# omnibus_proto.net
KiCad netlist of a schematic drawn in EAGLE
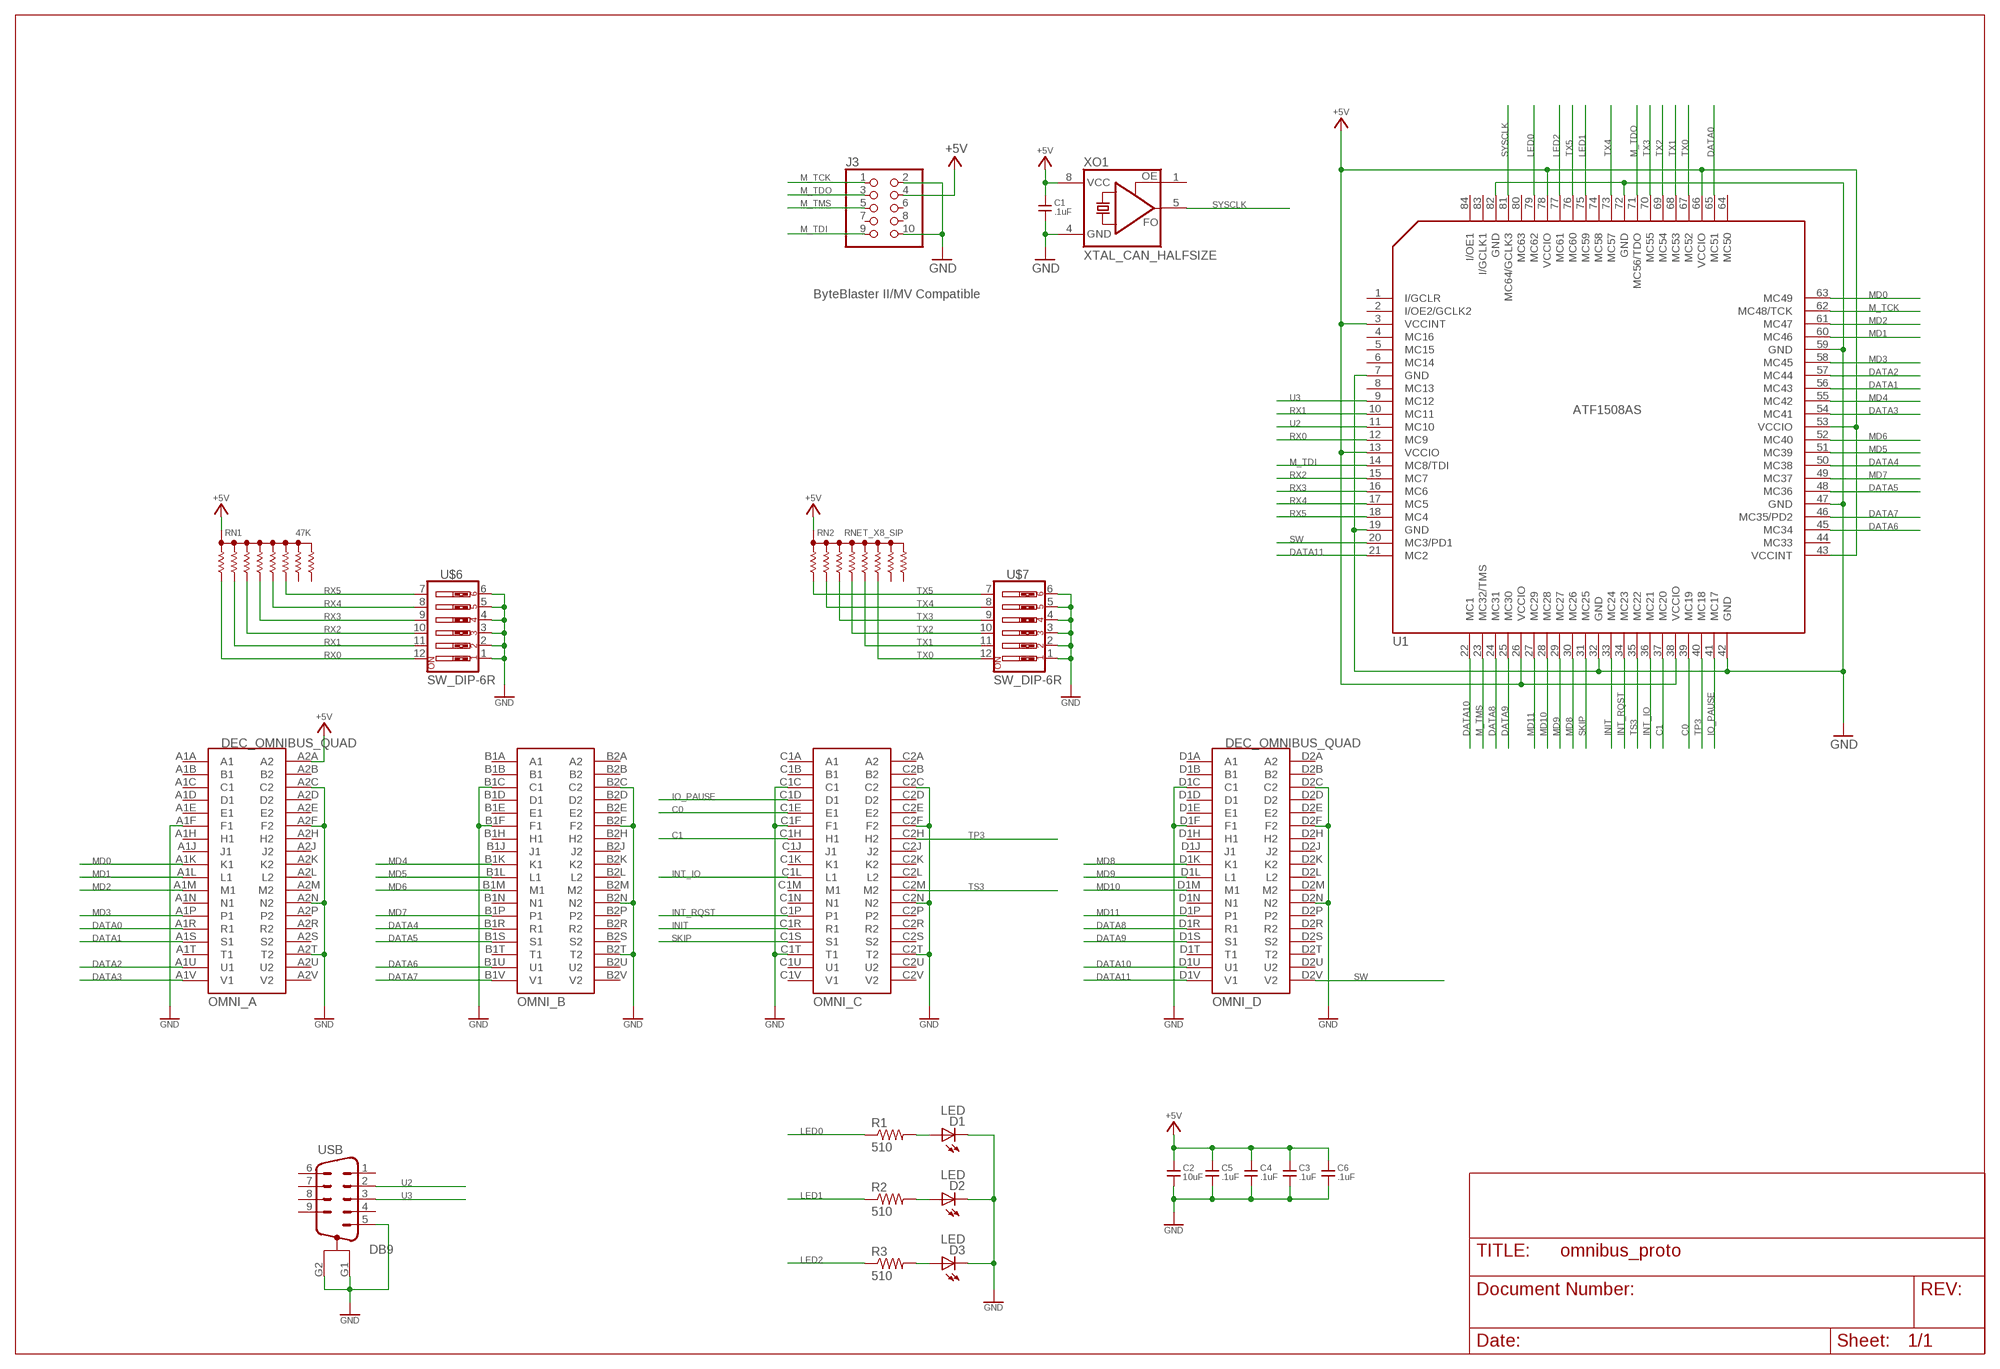
[diagram p0: schematic, sheet 1]

(export (version "E")
  (design (tool "Eeschema 10.0.6"))
  (components
    (comp (ref "C1")
      (value ".1uF")
      (footprint "eagle-import:C_TH_5MM")
      (libsource (lib "eagle-import") (part "C_US"))
    )
    (comp (ref "C2")
      (value "10uF")
      (footprint "eagle-import:C_TH_5MM")
      (libsource (lib "eagle-import") (part "C_US"))
    )
    (comp (ref "C3")
      (value ".1uF")
      (footprint "eagle-import:C_TH_5MM")
      (libsource (lib "eagle-import") (part "C_US"))
    )
    (comp (ref "C4")
      (value ".1uF")
      (footprint "eagle-import:C_TH_5MM")
      (libsource (lib "eagle-import") (part "C_US"))
    )
    (comp (ref "C5")
      (value ".1uF")
      (footprint "eagle-import:C_TH_5MM")
      (libsource (lib "eagle-import") (part "C_US"))
    )
    (comp (ref "C6")
      (value ".1uF")
      (footprint "eagle-import:C_TH_5MM")
      (libsource (lib "eagle-import") (part "C_US"))
    )
    (comp (ref "D1")
      (value "LED")
      (footprint "eagle-import:LED_TH_3MM")
      (libsource (lib "eagle-import") (part "LED"))
    )
    (comp (ref "D2")
      (value "LED")
      (footprint "eagle-import:LED_TH_3MM")
      (libsource (lib "eagle-import") (part "LED"))
    )
    (comp (ref "D3")
      (value "LED")
      (footprint "eagle-import:LED_TH_3MM")
      (libsource (lib "eagle-import") (part "LED"))
    )
    (comp (ref "J3")
      (value "HDR_2X5\"")
      (footprint "eagle-import:HDR_2X5")
      (libsource (lib "eagle-import") (part "HDR_2X5{dblquote}"))
    )
    (comp (ref "OMNI")
      (value "DEC_OMNIBUS_QUAD")
      (footprint "eagle-import:DEC_OMNIBUS_QUAD")
      (libsource (lib "eagle-import") (part "DEC_OMNIBUS_QUAD"))
    )
    (comp (ref "R1")
      (value "510")
      (footprint "eagle-import:R_204_7")
      (libsource (lib "eagle-import") (part "R_US"))
    )
    (comp (ref "R2")
      (value "510")
      (footprint "eagle-import:R_204_7")
      (libsource (lib "eagle-import") (part "R_US"))
    )
    (comp (ref "R3")
      (value "510")
      (footprint "eagle-import:R_204_7")
      (libsource (lib "eagle-import") (part "R_US"))
    )
    (comp (ref "RN1")
      (value "47K")
      (footprint "eagle-import:RN_SIP9")
      (libsource (lib "eagle-import") (part "RNET_X8_SIP"))
    )
    (comp (ref "RN2")
      (value "RNET_X8_SIP")
      (footprint "eagle-import:RN_SIP9")
      (libsource (lib "eagle-import") (part "RNET_X8_SIP"))
    )
    (comp (ref "U$6")
      (value "SW_DIP-6R")
      (footprint "eagle-import:SW_DIP-6_ROUND")
      (libsource (lib "eagle-import") (part "SW_DIP-6R"))
    )
    (comp (ref "U$7")
      (value "SW_DIP-6R")
      (footprint "eagle-import:SW_DIP-6_ROUND")
      (libsource (lib "eagle-import") (part "SW_DIP-6R"))
    )
    (comp (ref "U1")
      (value "ATF1508AS")
      (footprint "eagle-import:PLCC84")
      (libsource (lib "eagle-import") (part "ATF1504AS_PLCC"))
    )
    (comp (ref "USB")
      (value "DB9")
      (footprint "eagle-import:AMP_DB-9RA")
      (fields (field (name "MANF") "TE/AMP"))
      (libsource (lib "eagle-import") (part "DB9"))
    )
    (comp (ref "XO1")
      (value "XTAL_CAN_HALFSIZE")
      (footprint "eagle-import:XTAL_CAN_HALFSIZE")
      (libsource (lib "eagle-import") (part "XTAL_CAN_HALFSIZE"))
    )
  )
  (nets
    (net (code "1") (name "+5V") (class "Default")
      (node (ref "C1") (pin "1") (pinfunction "1_1") (pintype "passive"))
      (node (ref "C2") (pin "1") (pinfunction "1_1") (pintype "passive"))
      (node (ref "C3") (pin "1") (pinfunction "1_1") (pintype "passive"))
      (node (ref "C4") (pin "1") (pinfunction "1_1") (pintype "passive"))
      (node (ref "C5") (pin "1") (pinfunction "1_1") (pintype "passive"))
      (node (ref "C6") (pin "1") (pinfunction "1_1") (pintype "passive"))
      (node (ref "J3") (pin "4") (pinfunction "4_4") (pintype "passive"))
      (node (ref "OMNI") (pin "A2A") (pinfunction "A2_A2A") (pintype "passive"))
      (node (ref "RN1") (pin "1") (pinfunction "1_1") (pintype "passive"))
      (node (ref "RN2") (pin "1") (pinfunction "1_1") (pintype "passive"))
      (node (ref "U1") (pin "13") (pinfunction "VCCIO_13") (pintype "bidirectional"))
      (node (ref "U1") (pin "26") (pinfunction "VCCIO_26") (pintype "bidirectional"))
      (node (ref "U1") (pin "3") (pinfunction "VCCINT_3") (pintype "bidirectional"))
      (node (ref "U1") (pin "38") (pinfunction "VCCIO_38") (pintype "bidirectional"))
      (node (ref "U1") (pin "43") (pinfunction "VCCINT_43") (pintype "bidirectional"))
      (node (ref "U1") (pin "53") (pinfunction "VCCIO_53") (pintype "bidirectional"))
      (node (ref "U1") (pin "66") (pinfunction "VCCIO_66") (pintype "bidirectional"))
      (node (ref "U1") (pin "78") (pinfunction "VCCIO_78") (pintype "bidirectional"))
      (node (ref "XO1") (pin "8") (pinfunction "VCC_8") (pintype "power_in"))
    )
    (net (code "2") (name "/C0") (class "Default")
      (node (ref "OMNI") (pin "C1E") (pinfunction "E1_C1E") (pintype "passive"))
      (node (ref "U1") (pin "39") (pinfunction "MC19_39") (pintype "bidirectional"))
    )
    (net (code "3") (name "/C1") (class "Default")
      (node (ref "OMNI") (pin "C1H") (pinfunction "H1_C1H") (pintype "passive"))
      (node (ref "U1") (pin "37") (pinfunction "MC20_37") (pintype "bidirectional"))
    )
    (net (code "4") (name "/DATA0") (class "Default")
      (node (ref "OMNI") (pin "A1R") (pinfunction "R1_A1R") (pintype "passive"))
      (node (ref "U1") (pin "65") (pinfunction "MC51_65") (pintype "bidirectional"))
    )
    (net (code "5") (name "/DATA1") (class "Default")
      (node (ref "OMNI") (pin "A1S") (pinfunction "S1_A1S") (pintype "passive"))
      (node (ref "U1") (pin "56") (pinfunction "MC43_56") (pintype "bidirectional"))
    )
    (net (code "6") (name "/DATA2") (class "Default")
      (node (ref "OMNI") (pin "A1U") (pinfunction "U1_A1U") (pintype "passive"))
      (node (ref "U1") (pin "57") (pinfunction "MC44_57") (pintype "bidirectional"))
    )
    (net (code "7") (name "/DATA3") (class "Default")
      (node (ref "OMNI") (pin "A1V") (pinfunction "V1_A1V") (pintype "passive"))
      (node (ref "U1") (pin "54") (pinfunction "MC41_54") (pintype "bidirectional"))
    )
    (net (code "8") (name "/DATA4") (class "Default")
      (node (ref "OMNI") (pin "B1R") (pinfunction "R1_B1R") (pintype "passive"))
      (node (ref "U1") (pin "50") (pinfunction "MC38_50") (pintype "bidirectional"))
    )
    (net (code "9") (name "/DATA5") (class "Default")
      (node (ref "OMNI") (pin "B1S") (pinfunction "S1_B1S") (pintype "passive"))
      (node (ref "U1") (pin "48") (pinfunction "MC36_48") (pintype "bidirectional"))
    )
    (net (code "10") (name "/DATA6") (class "Default")
      (node (ref "OMNI") (pin "B1U") (pinfunction "U1_B1U") (pintype "passive"))
      (node (ref "U1") (pin "45") (pinfunction "MC34_45") (pintype "bidirectional"))
    )
    (net (code "11") (name "/DATA7") (class "Default")
      (node (ref "OMNI") (pin "B1V") (pinfunction "V1_B1V") (pintype "passive"))
      (node (ref "U1") (pin "46") (pinfunction "MC35/PD2_46") (pintype "bidirectional"))
    )
    (net (code "12") (name "/DATA8") (class "Default")
      (node (ref "OMNI") (pin "D1R") (pinfunction "R1_D1R") (pintype "passive"))
      (node (ref "U1") (pin "24") (pinfunction "MC31_24") (pintype "bidirectional"))
    )
    (net (code "13") (name "/DATA9") (class "Default")
      (node (ref "OMNI") (pin "D1S") (pinfunction "S1_D1S") (pintype "passive"))
      (node (ref "U1") (pin "25") (pinfunction "MC30_25") (pintype "bidirectional"))
    )
    (net (code "14") (name "/DATA10") (class "Default")
      (node (ref "OMNI") (pin "D1U") (pinfunction "U1_D1U") (pintype "passive"))
      (node (ref "U1") (pin "22") (pinfunction "MC1_22") (pintype "bidirectional"))
    )
    (net (code "15") (name "/DATA11") (class "Default")
      (node (ref "OMNI") (pin "D1V") (pinfunction "V1_D1V") (pintype "passive"))
      (node (ref "U1") (pin "21") (pinfunction "MC2_21") (pintype "bidirectional"))
    )
    (net (code "16") (name "/INIT") (class "Default")
      (node (ref "OMNI") (pin "C1R") (pinfunction "R1_C1R") (pintype "passive"))
      (node (ref "U1") (pin "33") (pinfunction "MC24_33") (pintype "bidirectional"))
    )
    (net (code "17") (name "/INT_IO") (class "Default")
      (node (ref "OMNI") (pin "C1L") (pinfunction "L1_C1L") (pintype "passive"))
      (node (ref "U1") (pin "36") (pinfunction "MC21_36") (pintype "bidirectional"))
    )
    (net (code "18") (name "/INT_RQST") (class "Default")
      (node (ref "OMNI") (pin "C1P") (pinfunction "P1_C1P") (pintype "passive"))
      (node (ref "U1") (pin "34") (pinfunction "MC23_34") (pintype "bidirectional"))
    )
    (net (code "19") (name "/IO_PAUSE") (class "Default")
      (node (ref "OMNI") (pin "C1D") (pinfunction "D1_C1D") (pintype "passive"))
      (node (ref "U1") (pin "41") (pinfunction "MC17_41") (pintype "bidirectional"))
    )
    (net (code "20") (name "/LED0") (class "Default")
      (node (ref "R1") (pin "1") (pinfunction "1_1") (pintype "passive"))
      (node (ref "U1") (pin "79") (pinfunction "MC62_79") (pintype "bidirectional"))
    )
    (net (code "21") (name "/LED1") (class "Default")
      (node (ref "R2") (pin "1") (pinfunction "1_1") (pintype "passive"))
      (node (ref "U1") (pin "75") (pinfunction "MC59_75") (pintype "bidirectional"))
    )
    (net (code "22") (name "/LED2") (class "Default")
      (node (ref "R3") (pin "1") (pinfunction "1_1") (pintype "passive"))
      (node (ref "U1") (pin "77") (pinfunction "MC61_77") (pintype "bidirectional"))
    )
    (net (code "23") (name "/MD0") (class "Default")
      (node (ref "OMNI") (pin "A1K") (pinfunction "K1_A1K") (pintype "passive"))
      (node (ref "U1") (pin "63") (pinfunction "MC49_63") (pintype "bidirectional"))
    )
    (net (code "24") (name "/MD1") (class "Default")
      (node (ref "OMNI") (pin "A1L") (pinfunction "L1_A1L") (pintype "passive"))
      (node (ref "U1") (pin "60") (pinfunction "MC46_60") (pintype "bidirectional"))
    )
    (net (code "25") (name "/MD2") (class "Default")
      (node (ref "OMNI") (pin "A1M") (pinfunction "M1_A1M") (pintype "passive"))
      (node (ref "U1") (pin "61") (pinfunction "MC47_61") (pintype "bidirectional"))
    )
    (net (code "26") (name "/MD3") (class "Default")
      (node (ref "OMNI") (pin "A1P") (pinfunction "P1_A1P") (pintype "passive"))
      (node (ref "U1") (pin "58") (pinfunction "MC45_58") (pintype "bidirectional"))
    )
    (net (code "27") (name "/MD4") (class "Default")
      (node (ref "OMNI") (pin "B1K") (pinfunction "K1_B1K") (pintype "passive"))
      (node (ref "U1") (pin "55") (pinfunction "MC42_55") (pintype "bidirectional"))
    )
    (net (code "28") (name "/MD5") (class "Default")
      (node (ref "OMNI") (pin "B1L") (pinfunction "L1_B1L") (pintype "passive"))
      (node (ref "U1") (pin "51") (pinfunction "MC39_51") (pintype "bidirectional"))
    )
    (net (code "29") (name "/MD6") (class "Default")
      (node (ref "OMNI") (pin "B1M") (pinfunction "M1_B1M") (pintype "passive"))
      (node (ref "U1") (pin "52") (pinfunction "MC40_52") (pintype "bidirectional"))
    )
    (net (code "30") (name "/MD7") (class "Default")
      (node (ref "OMNI") (pin "B1P") (pinfunction "P1_B1P") (pintype "passive"))
      (node (ref "U1") (pin "49") (pinfunction "MC37_49") (pintype "bidirectional"))
    )
    (net (code "31") (name "/MD8") (class "Default")
      (node (ref "OMNI") (pin "D1K") (pinfunction "K1_D1K") (pintype "passive"))
      (node (ref "U1") (pin "30") (pinfunction "MC26_30") (pintype "bidirectional"))
    )
    (net (code "32") (name "/MD9") (class "Default")
      (node (ref "OMNI") (pin "D1L") (pinfunction "L1_D1L") (pintype "passive"))
      (node (ref "U1") (pin "29") (pinfunction "MC27_29") (pintype "bidirectional"))
    )
    (net (code "33") (name "/MD10") (class "Default")
      (node (ref "OMNI") (pin "D1M") (pinfunction "M1_D1M") (pintype "passive"))
      (node (ref "U1") (pin "28") (pinfunction "MC28_28") (pintype "bidirectional"))
    )
    (net (code "34") (name "/MD11") (class "Default")
      (node (ref "OMNI") (pin "D1P") (pinfunction "P1_D1P") (pintype "passive"))
      (node (ref "U1") (pin "27") (pinfunction "MC29_27") (pintype "bidirectional"))
    )
    (net (code "35") (name "/M_TCK") (class "Default")
      (node (ref "J3") (pin "1") (pinfunction "1_1") (pintype "passive"))
      (node (ref "U1") (pin "62") (pinfunction "MC48/TCK_62") (pintype "bidirectional"))
    )
    (net (code "36") (name "/M_TDI") (class "Default")
      (node (ref "J3") (pin "9") (pinfunction "9_9") (pintype "passive"))
      (node (ref "U1") (pin "14") (pinfunction "MC8/TDI_14") (pintype "bidirectional"))
    )
    (net (code "37") (name "/M_TDO") (class "Default")
      (node (ref "J3") (pin "3") (pinfunction "3_3") (pintype "passive"))
      (node (ref "U1") (pin "71") (pinfunction "MC56/TDO_71") (pintype "bidirectional"))
    )
    (net (code "38") (name "/M_TMS") (class "Default")
      (node (ref "J3") (pin "5") (pinfunction "5_5") (pintype "passive"))
      (node (ref "U1") (pin "23") (pinfunction "MC32/TMS_23") (pintype "bidirectional"))
    )
    (net (code "39") (name "/RX0") (class "Default")
      (node (ref "RN1") (pin "2") (pinfunction "2_2") (pintype "passive"))
      (node (ref "U$6") (pin "12") (pinfunction "12_12") (pintype "passive"))
      (node (ref "U1") (pin "12") (pinfunction "MC9_12") (pintype "bidirectional"))
    )
    (net (code "40") (name "/RX1") (class "Default")
      (node (ref "RN1") (pin "3") (pinfunction "3_3") (pintype "passive"))
      (node (ref "U$6") (pin "11") (pinfunction "11_11") (pintype "passive"))
      (node (ref "U1") (pin "10") (pinfunction "MC11_10") (pintype "bidirectional"))
    )
    (net (code "41") (name "/RX2") (class "Default")
      (node (ref "RN1") (pin "4") (pinfunction "4_4") (pintype "passive"))
      (node (ref "U$6") (pin "10") (pinfunction "10_10") (pintype "passive"))
      (node (ref "U1") (pin "15") (pinfunction "MC7_15") (pintype "bidirectional"))
    )
    (net (code "42") (name "/RX3") (class "Default")
      (node (ref "RN1") (pin "5") (pinfunction "5_5") (pintype "passive"))
      (node (ref "U$6") (pin "9") (pinfunction "9_9") (pintype "passive"))
      (node (ref "U1") (pin "16") (pinfunction "MC6_16") (pintype "bidirectional"))
    )
    (net (code "43") (name "/RX4") (class "Default")
      (node (ref "RN1") (pin "6") (pinfunction "6_6") (pintype "passive"))
      (node (ref "U$6") (pin "8") (pinfunction "8_8") (pintype "passive"))
      (node (ref "U1") (pin "17") (pinfunction "MC5_17") (pintype "bidirectional"))
    )
    (net (code "44") (name "/RX5") (class "Default")
      (node (ref "RN1") (pin "7") (pinfunction "7_7") (pintype "passive"))
      (node (ref "U$6") (pin "7") (pinfunction "7_7") (pintype "passive"))
      (node (ref "U1") (pin "18") (pinfunction "MC4_18") (pintype "bidirectional"))
    )
    (net (code "45") (name "/SKIP") (class "Default")
      (node (ref "OMNI") (pin "C1S") (pinfunction "S1_C1S") (pintype "passive"))
      (node (ref "U1") (pin "31") (pinfunction "MC25_31") (pintype "bidirectional"))
    )
    (net (code "46") (name "/SW") (class "Default")
      (node (ref "OMNI") (pin "D2V") (pinfunction "V2_D2V") (pintype "passive"))
      (node (ref "U1") (pin "20") (pinfunction "MC3/PD1_20") (pintype "bidirectional"))
    )
    (net (code "47") (name "/SYSCLK") (class "Default")
      (node (ref "U1") (pin "81") (pinfunction "MC64/GCLK3_81") (pintype "bidirectional"))
      (node (ref "XO1") (pin "5") (pinfunction "FO_5") (pintype "output"))
    )
    (net (code "48") (name "/TP3") (class "Default")
      (node (ref "OMNI") (pin "C2H") (pinfunction "H2_C2H") (pintype "passive"))
      (node (ref "U1") (pin "40") (pinfunction "MC18_40") (pintype "bidirectional"))
    )
    (net (code "49") (name "/TS3") (class "Default")
      (node (ref "OMNI") (pin "C2M") (pinfunction "M2_C2M") (pintype "passive"))
      (node (ref "U1") (pin "35") (pinfunction "MC22_35") (pintype "bidirectional"))
    )
    (net (code "50") (name "/TX0") (class "Default")
      (node (ref "RN2") (pin "7") (pinfunction "7_7") (pintype "passive"))
      (node (ref "U$7") (pin "12") (pinfunction "12_12") (pintype "passive"))
      (node (ref "U1") (pin "67") (pinfunction "MC52_67") (pintype "bidirectional"))
    )
    (net (code "51") (name "/TX1") (class "Default")
      (node (ref "RN2") (pin "6") (pinfunction "6_6") (pintype "passive"))
      (node (ref "U$7") (pin "11") (pinfunction "11_11") (pintype "passive"))
      (node (ref "U1") (pin "68") (pinfunction "MC53_68") (pintype "bidirectional"))
    )
    (net (code "52") (name "/TX2") (class "Default")
      (node (ref "RN2") (pin "5") (pinfunction "5_5") (pintype "passive"))
      (node (ref "U$7") (pin "10") (pinfunction "10_10") (pintype "passive"))
      (node (ref "U1") (pin "69") (pinfunction "MC54_69") (pintype "bidirectional"))
    )
    (net (code "53") (name "/TX3") (class "Default")
      (node (ref "RN2") (pin "4") (pinfunction "4_4") (pintype "passive"))
      (node (ref "U$7") (pin "9") (pinfunction "9_9") (pintype "passive"))
      (node (ref "U1") (pin "70") (pinfunction "MC55_70") (pintype "bidirectional"))
    )
    (net (code "54") (name "/TX4") (class "Default")
      (node (ref "RN2") (pin "3") (pinfunction "3_3") (pintype "passive"))
      (node (ref "U$7") (pin "8") (pinfunction "8_8") (pintype "passive"))
      (node (ref "U1") (pin "73") (pinfunction "MC57_73") (pintype "bidirectional"))
    )
    (net (code "55") (name "/TX5") (class "Default")
      (node (ref "RN2") (pin "2") (pinfunction "2_2") (pintype "passive"))
      (node (ref "U$7") (pin "7") (pinfunction "7_7") (pintype "passive"))
      (node (ref "U1") (pin "76") (pinfunction "MC60_76") (pintype "bidirectional"))
    )
    (net (code "56") (name "/U2") (class "Default")
      (node (ref "U1") (pin "11") (pinfunction "MC10_11") (pintype "bidirectional"))
      (node (ref "USB") (pin "2") (pinfunction "2_2") (pintype "passive"))
    )
    (net (code "57") (name "/U3") (class "Default")
      (node (ref "U1") (pin "9") (pinfunction "MC12_9") (pintype "bidirectional"))
      (node (ref "USB") (pin "3") (pinfunction "3_3") (pintype "passive"))
    )
    (net (code "58") (name "GND") (class "Default")
      (node (ref "C1") (pin "2") (pinfunction "2_2") (pintype "passive"))
      (node (ref "C2") (pin "2") (pinfunction "2_2") (pintype "passive"))
      (node (ref "C3") (pin "2") (pinfunction "2_2") (pintype "passive"))
      (node (ref "C4") (pin "2") (pinfunction "2_2") (pintype "passive"))
      (node (ref "C5") (pin "2") (pinfunction "2_2") (pintype "passive"))
      (node (ref "C6") (pin "2") (pinfunction "2_2") (pintype "passive"))
      (node (ref "D1") (pin "K") (pinfunction "C_K") (pintype "passive"))
      (node (ref "D2") (pin "K") (pinfunction "C_K") (pintype "passive"))
      (node (ref "D3") (pin "K") (pinfunction "C_K") (pintype "passive"))
      (node (ref "J3") (pin "10") (pinfunction "10_10") (pintype "passive"))
      (node (ref "J3") (pin "2") (pinfunction "2_2") (pintype "passive"))
      (node (ref "OMNI") (pin "A1F") (pinfunction "F1_A1F") (pintype "passive"))
      (node (ref "OMNI") (pin "A2C") (pinfunction "C2_A2C") (pintype "passive"))
      (node (ref "OMNI") (pin "A2F") (pinfunction "F2_A2F") (pintype "passive"))
      (node (ref "OMNI") (pin "A2N") (pinfunction "N2_A2N") (pintype "passive"))
      (node (ref "OMNI") (pin "A2T") (pinfunction "T2_A2T") (pintype "passive"))
      (node (ref "OMNI") (pin "B1C") (pinfunction "C1_B1C") (pintype "passive"))
      (node (ref "OMNI") (pin "B1F") (pinfunction "F1_B1F") (pintype "passive"))
      (node (ref "OMNI") (pin "B2C") (pinfunction "C2_B2C") (pintype "passive"))
      (node (ref "OMNI") (pin "B2F") (pinfunction "F2_B2F") (pintype "passive"))
      (node (ref "OMNI") (pin "B2N") (pinfunction "N2_B2N") (pintype "passive"))
      (node (ref "OMNI") (pin "B2T") (pinfunction "T2_B2T") (pintype "passive"))
      (node (ref "OMNI") (pin "C1C") (pinfunction "C1_C1C") (pintype "passive"))
      (node (ref "OMNI") (pin "C1F") (pinfunction "F1_C1F") (pintype "passive"))
      (node (ref "OMNI") (pin "C1T") (pinfunction "T1_C1T") (pintype "passive"))
      (node (ref "OMNI") (pin "C2C") (pinfunction "C2_C2C") (pintype "passive"))
      (node (ref "OMNI") (pin "C2F") (pinfunction "F2_C2F") (pintype "passive"))
      (node (ref "OMNI") (pin "C2N") (pinfunction "N2_C2N") (pintype "passive"))
      (node (ref "OMNI") (pin "C2T") (pinfunction "T2_C2T") (pintype "passive"))
      (node (ref "OMNI") (pin "D1C") (pinfunction "C1_D1C") (pintype "passive"))
      (node (ref "OMNI") (pin "D1F") (pinfunction "F1_D1F") (pintype "passive"))
      (node (ref "OMNI") (pin "D2C") (pinfunction "C2_D2C") (pintype "passive"))
      (node (ref "OMNI") (pin "D2F") (pinfunction "F2_D2F") (pintype "passive"))
      (node (ref "OMNI") (pin "D2N") (pinfunction "N2_D2N") (pintype "passive"))
      (node (ref "U$6") (pin "1") (pinfunction "1_1") (pintype "passive"))
      (node (ref "U$6") (pin "2") (pinfunction "2_2") (pintype "passive"))
      (node (ref "U$6") (pin "3") (pinfunction "3_3") (pintype "passive"))
      (node (ref "U$6") (pin "4") (pinfunction "4_4") (pintype "passive"))
      (node (ref "U$6") (pin "5") (pinfunction "5_5") (pintype "passive"))
      (node (ref "U$6") (pin "6") (pinfunction "6_6") (pintype "passive"))
      (node (ref "U$7") (pin "1") (pinfunction "1_1") (pintype "passive"))
      (node (ref "U$7") (pin "2") (pinfunction "2_2") (pintype "passive"))
      (node (ref "U$7") (pin "3") (pinfunction "3_3") (pintype "passive"))
      (node (ref "U$7") (pin "4") (pinfunction "4_4") (pintype "passive"))
      (node (ref "U$7") (pin "5") (pinfunction "5_5") (pintype "passive"))
      (node (ref "U$7") (pin "6") (pinfunction "6_6") (pintype "passive"))
      (node (ref "U1") (pin "19") (pinfunction "GND_19") (pintype "bidirectional"))
      (node (ref "U1") (pin "32") (pinfunction "GND_32") (pintype "bidirectional"))
      (node (ref "U1") (pin "42") (pinfunction "GND_42") (pintype "bidirectional"))
      (node (ref "U1") (pin "47") (pinfunction "GND_47") (pintype "bidirectional"))
      (node (ref "U1") (pin "59") (pinfunction "GND_59") (pintype "bidirectional"))
      (node (ref "U1") (pin "7") (pinfunction "GND_7") (pintype "bidirectional"))
      (node (ref "U1") (pin "72") (pinfunction "GND_72") (pintype "bidirectional"))
      (node (ref "U1") (pin "82") (pinfunction "GND_82") (pintype "bidirectional"))
      (node (ref "USB") (pin "5") (pinfunction "5_5") (pintype "passive"))
      (node (ref "USB") (pin "G1") (pinfunction "G1_G1") (pintype "passive"))
      (node (ref "USB") (pin "G2") (pinfunction "G2_G2") (pintype "passive"))
      (node (ref "XO1") (pin "4") (pinfunction "GND_4") (pintype "power_in"))
    )
    (net (code "59") (name "Net-(D1-PadA)") (class "Default")
      (node (ref "D1") (pin "A") (pinfunction "A_A") (pintype "passive"))
      (node (ref "R1") (pin "2") (pinfunction "2_2") (pintype "passive"))
    )
    (net (code "60") (name "Net-(D2-PadA)") (class "Default")
      (node (ref "D2") (pin "A") (pinfunction "A_A") (pintype "passive"))
      (node (ref "R2") (pin "2") (pinfunction "2_2") (pintype "passive"))
    )
    (net (code "61") (name "Net-(D3-PadA)") (class "Default")
      (node (ref "D3") (pin "A") (pinfunction "A_A") (pintype "passive"))
      (node (ref "R3") (pin "2") (pinfunction "2_2") (pintype "passive"))
    )
    (net (code "62") (name "unconnected-(J3-Pad6)") (class "Default")
      (node (ref "J3") (pin "6") (pinfunction "6_6") (pintype "passive"))
    )
    (net (code "63") (name "unconnected-(J3-Pad7)") (class "Default")
      (node (ref "J3") (pin "7") (pinfunction "7_7") (pintype "passive"))
    )
    (net (code "64") (name "unconnected-(J3-Pad8)") (class "Default")
      (node (ref "J3") (pin "8") (pinfunction "8_8") (pintype "passive"))
    )
    (net (code "65") (name "unconnected-(OMNIA-A1-PadA1A)") (class "Default")
      (node (ref "OMNI") (pin "A1A") (pinfunction "A1_A1A") (pintype "passive"))
    )
    (net (code "66") (name "unconnected-(OMNIA-B1-PadA1B)") (class "Default")
      (node (ref "OMNI") (pin "A1B") (pinfunction "B1_A1B") (pintype "passive"))
    )
    (net (code "67") (name "unconnected-(OMNIA-B2-PadA2B)") (class "Default")
      (node (ref "OMNI") (pin "A2B") (pinfunction "B2_A2B") (pintype "passive"))
    )
    (net (code "68") (name "unconnected-(OMNIA-C1-PadA1C)") (class "Default")
      (node (ref "OMNI") (pin "A1C") (pinfunction "C1_A1C") (pintype "passive"))
    )
    (net (code "69") (name "unconnected-(OMNIA-D1-PadA1D)") (class "Default")
      (node (ref "OMNI") (pin "A1D") (pinfunction "D1_A1D") (pintype "passive"))
    )
    (net (code "70") (name "unconnected-(OMNIA-D2-PadA2D)") (class "Default")
      (node (ref "OMNI") (pin "A2D") (pinfunction "D2_A2D") (pintype "passive"))
    )
    (net (code "71") (name "unconnected-(OMNIA-E1-PadA1E)") (class "Default")
      (node (ref "OMNI") (pin "A1E") (pinfunction "E1_A1E") (pintype "passive"))
    )
    (net (code "72") (name "unconnected-(OMNIA-E2-PadA2E)") (class "Default")
      (node (ref "OMNI") (pin "A2E") (pinfunction "E2_A2E") (pintype "passive"))
    )
    (net (code "73") (name "unconnected-(OMNIA-H1-PadA1H)") (class "Default")
      (node (ref "OMNI") (pin "A1H") (pinfunction "H1_A1H") (pintype "passive"))
    )
    (net (code "74") (name "unconnected-(OMNIA-H2-PadA2H)") (class "Default")
      (node (ref "OMNI") (pin "A2H") (pinfunction "H2_A2H") (pintype "passive"))
    )
    (net (code "75") (name "unconnected-(OMNIA-J1-PadA1J)") (class "Default")
      (node (ref "OMNI") (pin "A1J") (pinfunction "J1_A1J") (pintype "passive"))
    )
    (net (code "76") (name "unconnected-(OMNIA-J2-PadA2J)") (class "Default")
      (node (ref "OMNI") (pin "A2J") (pinfunction "J2_A2J") (pintype "passive"))
    )
    (net (code "77") (name "unconnected-(OMNIA-K2-PadA2K)") (class "Default")
      (node (ref "OMNI") (pin "A2K") (pinfunction "K2_A2K") (pintype "passive"))
    )
    (net (code "78") (name "unconnected-(OMNIA-L2-PadA2L)") (class "Default")
      (node (ref "OMNI") (pin "A2L") (pinfunction "L2_A2L") (pintype "passive"))
    )
    (net (code "79") (name "unconnected-(OMNIA-M2-PadA2M)") (class "Default")
      (node (ref "OMNI") (pin "A2M") (pinfunction "M2_A2M") (pintype "passive"))
    )
    (net (code "80") (name "unconnected-(OMNIA-N1-PadA1N)") (class "Default")
      (node (ref "OMNI") (pin "A1N") (pinfunction "N1_A1N") (pintype "passive"))
    )
    (net (code "81") (name "unconnected-(OMNIA-P2-PadA2P)") (class "Default")
      (node (ref "OMNI") (pin "A2P") (pinfunction "P2_A2P") (pintype "passive"))
    )
    (net (code "82") (name "unconnected-(OMNIA-R2-PadA2R)") (class "Default")
      (node (ref "OMNI") (pin "A2R") (pinfunction "R2_A2R") (pintype "passive"))
    )
    (net (code "83") (name "unconnected-(OMNIA-S2-PadA2S)") (class "Default")
      (node (ref "OMNI") (pin "A2S") (pinfunction "S2_A2S") (pintype "passive"))
    )
    (net (code "84") (name "unconnected-(OMNIA-T1-PadA1T)") (class "Default")
      (node (ref "OMNI") (pin "A1T") (pinfunction "T1_A1T") (pintype "passive"))
    )
    (net (code "85") (name "unconnected-(OMNIA-U2-PadA2U)") (class "Default")
      (node (ref "OMNI") (pin "A2U") (pinfunction "U2_A2U") (pintype "passive"))
    )
    (net (code "86") (name "unconnected-(OMNIA-V2-PadA2V)") (class "Default")
      (node (ref "OMNI") (pin "A2V") (pinfunction "V2_A2V") (pintype "passive"))
    )
    (net (code "87") (name "unconnected-(OMNIB-A1-PadB1A)") (class "Default")
      (node (ref "OMNI") (pin "B1A") (pinfunction "A1_B1A") (pintype "passive"))
    )
    (net (code "88") (name "unconnected-(OMNIB-A2-PadB2A)") (class "Default")
      (node (ref "OMNI") (pin "B2A") (pinfunction "A2_B2A") (pintype "passive"))
    )
    (net (code "89") (name "unconnected-(OMNIB-B1-PadB1B)") (class "Default")
      (node (ref "OMNI") (pin "B1B") (pinfunction "B1_B1B") (pintype "passive"))
    )
    (net (code "90") (name "unconnected-(OMNIB-B2-PadB2B)") (class "Default")
      (node (ref "OMNI") (pin "B2B") (pinfunction "B2_B2B") (pintype "passive"))
    )
    (net (code "91") (name "unconnected-(OMNIB-D1-PadB1D)") (class "Default")
      (node (ref "OMNI") (pin "B1D") (pinfunction "D1_B1D") (pintype "passive"))
    )
    (net (code "92") (name "unconnected-(OMNIB-D2-PadB2D)") (class "Default")
      (node (ref "OMNI") (pin "B2D") (pinfunction "D2_B2D") (pintype "passive"))
    )
    (net (code "93") (name "unconnected-(OMNIB-E1-PadB1E)") (class "Default")
      (node (ref "OMNI") (pin "B1E") (pinfunction "E1_B1E") (pintype "passive"))
    )
    (net (code "94") (name "unconnected-(OMNIB-E2-PadB2E)") (class "Default")
      (node (ref "OMNI") (pin "B2E") (pinfunction "E2_B2E") (pintype "passive"))
    )
    (net (code "95") (name "unconnected-(OMNIB-H1-PadB1H)") (class "Default")
      (node (ref "OMNI") (pin "B1H") (pinfunction "H1_B1H") (pintype "passive"))
    )
    (net (code "96") (name "unconnected-(OMNIB-H2-PadB2H)") (class "Default")
      (node (ref "OMNI") (pin "B2H") (pinfunction "H2_B2H") (pintype "passive"))
    )
    (net (code "97") (name "unconnected-(OMNIB-J1-PadB1J)") (class "Default")
      (node (ref "OMNI") (pin "B1J") (pinfunction "J1_B1J") (pintype "passive"))
    )
    (net (code "98") (name "unconnected-(OMNIB-J2-PadB2J)") (class "Default")
      (node (ref "OMNI") (pin "B2J") (pinfunction "J2_B2J") (pintype "passive"))
    )
    (net (code "99") (name "unconnected-(OMNIB-K2-PadB2K)") (class "Default")
      (node (ref "OMNI") (pin "B2K") (pinfunction "K2_B2K") (pintype "passive"))
    )
    (net (code "100") (name "unconnected-(OMNIB-L2-PadB2L)") (class "Default")
      (node (ref "OMNI") (pin "B2L") (pinfunction "L2_B2L") (pintype "passive"))
    )
    (net (code "101") (name "unconnected-(OMNIB-M2-PadB2M)") (class "Default")
      (node (ref "OMNI") (pin "B2M") (pinfunction "M2_B2M") (pintype "passive"))
    )
    (net (code "102") (name "unconnected-(OMNIB-N1-PadB1N)") (class "Default")
      (node (ref "OMNI") (pin "B1N") (pinfunction "N1_B1N") (pintype "passive"))
    )
    (net (code "103") (name "unconnected-(OMNIB-P2-PadB2P)") (class "Default")
      (node (ref "OMNI") (pin "B2P") (pinfunction "P2_B2P") (pintype "passive"))
    )
    (net (code "104") (name "unconnected-(OMNIB-R2-PadB2R)") (class "Default")
      (node (ref "OMNI") (pin "B2R") (pinfunction "R2_B2R") (pintype "passive"))
    )
    (net (code "105") (name "unconnected-(OMNIB-S2-PadB2S)") (class "Default")
      (node (ref "OMNI") (pin "B2S") (pinfunction "S2_B2S") (pintype "passive"))
    )
    (net (code "106") (name "unconnected-(OMNIB-T1-PadB1T)") (class "Default")
      (node (ref "OMNI") (pin "B1T") (pinfunction "T1_B1T") (pintype "passive"))
    )
    (net (code "107") (name "unconnected-(OMNIB-U2-PadB2U)") (class "Default")
      (node (ref "OMNI") (pin "B2U") (pinfunction "U2_B2U") (pintype "passive"))
    )
    (net (code "108") (name "unconnected-(OMNIB-V2-PadB2V)") (class "Default")
      (node (ref "OMNI") (pin "B2V") (pinfunction "V2_B2V") (pintype "passive"))
    )
    (net (code "109") (name "unconnected-(OMNIC-A1-PadC1A)") (class "Default")
      (node (ref "OMNI") (pin "C1A") (pinfunction "A1_C1A") (pintype "passive"))
    )
    (net (code "110") (name "unconnected-(OMNIC-A2-PadC2A)") (class "Default")
      (node (ref "OMNI") (pin "C2A") (pinfunction "A2_C2A") (pintype "passive"))
    )
    (net (code "111") (name "unconnected-(OMNIC-B1-PadC1B)") (class "Default")
      (node (ref "OMNI") (pin "C1B") (pinfunction "B1_C1B") (pintype "passive"))
    )
    (net (code "112") (name "unconnected-(OMNIC-B2-PadC2B)") (class "Default")
      (node (ref "OMNI") (pin "C2B") (pinfunction "B2_C2B") (pintype "passive"))
    )
    (net (code "113") (name "unconnected-(OMNIC-D2-PadC2D)") (class "Default")
      (node (ref "OMNI") (pin "C2D") (pinfunction "D2_C2D") (pintype "passive"))
    )
    (net (code "114") (name "unconnected-(OMNIC-E2-PadC2E)") (class "Default")
      (node (ref "OMNI") (pin "C2E") (pinfunction "E2_C2E") (pintype "passive"))
    )
    (net (code "115") (name "unconnected-(OMNIC-J1-PadC1J)") (class "Default")
      (node (ref "OMNI") (pin "C1J") (pinfunction "J1_C1J") (pintype "passive"))
    )
    (net (code "116") (name "unconnected-(OMNIC-J2-PadC2J)") (class "Default")
      (node (ref "OMNI") (pin "C2J") (pinfunction "J2_C2J") (pintype "passive"))
    )
    (net (code "117") (name "unconnected-(OMNIC-K1-PadC1K)") (class "Default")
      (node (ref "OMNI") (pin "C1K") (pinfunction "K1_C1K") (pintype "passive"))
    )
    (net (code "118") (name "unconnected-(OMNIC-K2-PadC2K)") (class "Default")
      (node (ref "OMNI") (pin "C2K") (pinfunction "K2_C2K") (pintype "passive"))
    )
    (net (code "119") (name "unconnected-(OMNIC-L2-PadC2L)") (class "Default")
      (node (ref "OMNI") (pin "C2L") (pinfunction "L2_C2L") (pintype "passive"))
    )
    (net (code "120") (name "unconnected-(OMNIC-M1-PadC1M)") (class "Default")
      (node (ref "OMNI") (pin "C1M") (pinfunction "M1_C1M") (pintype "passive"))
    )
    (net (code "121") (name "unconnected-(OMNIC-N1-PadC1N)") (class "Default")
      (node (ref "OMNI") (pin "C1N") (pinfunction "N1_C1N") (pintype "passive"))
    )
    (net (code "122") (name "unconnected-(OMNIC-P2-PadC2P)") (class "Default")
      (node (ref "OMNI") (pin "C2P") (pinfunction "P2_C2P") (pintype "passive"))
    )
    (net (code "123") (name "unconnected-(OMNIC-R2-PadC2R)") (class "Default")
      (node (ref "OMNI") (pin "C2R") (pinfunction "R2_C2R") (pintype "passive"))
    )
    (net (code "124") (name "unconnected-(OMNIC-S2-PadC2S)") (class "Default")
      (node (ref "OMNI") (pin "C2S") (pinfunction "S2_C2S") (pintype "passive"))
    )
    (net (code "125") (name "unconnected-(OMNIC-U1-PadC1U)") (class "Default")
      (node (ref "OMNI") (pin "C1U") (pinfunction "U1_C1U") (pintype "passive"))
    )
    (net (code "126") (name "unconnected-(OMNIC-U2-PadC2U)") (class "Default")
      (node (ref "OMNI") (pin "C2U") (pinfunction "U2_C2U") (pintype "passive"))
    )
    (net (code "127") (name "unconnected-(OMNIC-V1-PadC1V)") (class "Default")
      (node (ref "OMNI") (pin "C1V") (pinfunction "V1_C1V") (pintype "passive"))
    )
    (net (code "128") (name "unconnected-(OMNIC-V2-PadC2V)") (class "Default")
      (node (ref "OMNI") (pin "C2V") (pinfunction "V2_C2V") (pintype "passive"))
    )
    (net (code "129") (name "unconnected-(OMNID-A1-PadD1A)") (class "Default")
      (node (ref "OMNI") (pin "D1A") (pinfunction "A1_D1A") (pintype "passive"))
    )
    (net (code "130") (name "unconnected-(OMNID-A2-PadD2A)") (class "Default")
      (node (ref "OMNI") (pin "D2A") (pinfunction "A2_D2A") (pintype "passive"))
    )
    (net (code "131") (name "unconnected-(OMNID-B1-PadD1B)") (class "Default")
      (node (ref "OMNI") (pin "D1B") (pinfunction "B1_D1B") (pintype "passive"))
    )
    (net (code "132") (name "unconnected-(OMNID-B2-PadD2B)") (class "Default")
      (node (ref "OMNI") (pin "D2B") (pinfunction "B2_D2B") (pintype "passive"))
    )
    (net (code "133") (name "unconnected-(OMNID-D1-PadD1D)") (class "Default")
      (node (ref "OMNI") (pin "D1D") (pinfunction "D1_D1D") (pintype "passive"))
    )
    (net (code "134") (name "unconnected-(OMNID-D2-PadD2D)") (class "Default")
      (node (ref "OMNI") (pin "D2D") (pinfunction "D2_D2D") (pintype "passive"))
    )
    (net (code "135") (name "unconnected-(OMNID-E1-PadD1E)") (class "Default")
      (node (ref "OMNI") (pin "D1E") (pinfunction "E1_D1E") (pintype "passive"))
    )
    (net (code "136") (name "unconnected-(OMNID-E2-PadD2E)") (class "Default")
      (node (ref "OMNI") (pin "D2E") (pinfunction "E2_D2E") (pintype "passive"))
    )
    (net (code "137") (name "unconnected-(OMNID-H1-PadD1H)") (class "Default")
      (node (ref "OMNI") (pin "D1H") (pinfunction "H1_D1H") (pintype "passive"))
    )
    (net (code "138") (name "unconnected-(OMNID-H2-PadD2H)") (class "Default")
      (node (ref "OMNI") (pin "D2H") (pinfunction "H2_D2H") (pintype "passive"))
    )
    (net (code "139") (name "unconnected-(OMNID-J1-PadD1J)") (class "Default")
      (node (ref "OMNI") (pin "D1J") (pinfunction "J1_D1J") (pintype "passive"))
    )
    (net (code "140") (name "unconnected-(OMNID-J2-PadD2J)") (class "Default")
      (node (ref "OMNI") (pin "D2J") (pinfunction "J2_D2J") (pintype "passive"))
    )
    (net (code "141") (name "unconnected-(OMNID-K2-PadD2K)") (class "Default")
      (node (ref "OMNI") (pin "D2K") (pinfunction "K2_D2K") (pintype "passive"))
    )
    (net (code "142") (name "unconnected-(OMNID-L2-PadD2L)") (class "Default")
      (node (ref "OMNI") (pin "D2L") (pinfunction "L2_D2L") (pintype "passive"))
    )
    (net (code "143") (name "unconnected-(OMNID-M2-PadD2M)") (class "Default")
      (node (ref "OMNI") (pin "D2M") (pinfunction "M2_D2M") (pintype "passive"))
    )
    (net (code "144") (name "unconnected-(OMNID-N1-PadD1N)") (class "Default")
      (node (ref "OMNI") (pin "D1N") (pinfunction "N1_D1N") (pintype "passive"))
    )
    (net (code "145") (name "unconnected-(OMNID-P2-PadD2P)") (class "Default")
      (node (ref "OMNI") (pin "D2P") (pinfunction "P2_D2P") (pintype "passive"))
    )
    (net (code "146") (name "unconnected-(OMNID-R2-PadD2R)") (class "Default")
      (node (ref "OMNI") (pin "D2R") (pinfunction "R2_D2R") (pintype "passive"))
    )
    (net (code "147") (name "unconnected-(OMNID-S2-PadD2S)") (class "Default")
      (node (ref "OMNI") (pin "D2S") (pinfunction "S2_D2S") (pintype "passive"))
    )
    (net (code "148") (name "unconnected-(OMNID-T1-PadD1T)") (class "Default")
      (node (ref "OMNI") (pin "D1T") (pinfunction "T1_D1T") (pintype "passive"))
    )
    (net (code "149") (name "unconnected-(OMNID-T2-PadD2T)") (class "Default")
      (node (ref "OMNI") (pin "D2T") (pinfunction "T2_D2T") (pintype "passive"))
    )
    (net (code "150") (name "unconnected-(OMNID-U2-PadD2U)") (class "Default")
      (node (ref "OMNI") (pin "D2U") (pinfunction "U2_D2U") (pintype "passive"))
    )
    (net (code "151") (name "unconnected-(RN1-Pad8)") (class "Default")
      (node (ref "RN1") (pin "8") (pinfunction "8_8") (pintype "passive"))
    )
    (net (code "152") (name "unconnected-(RN1-Pad9)") (class "Default")
      (node (ref "RN1") (pin "9") (pinfunction "9_9") (pintype "passive"))
    )
    (net (code "153") (name "unconnected-(RN2-Pad8)") (class "Default")
      (node (ref "RN2") (pin "8") (pinfunction "8_8") (pintype "passive"))
    )
    (net (code "154") (name "unconnected-(RN2-Pad9)") (class "Default")
      (node (ref "RN2") (pin "9") (pinfunction "9_9") (pintype "passive"))
    )
    (net (code "155") (name "unconnected-(U1-I{slash}GCLK1-Pad83)") (class "Default")
      (node (ref "U1") (pin "83") (pinfunction "I/GCLK1_83") (pintype "bidirectional"))
    )
    (net (code "156") (name "unconnected-(U1-I{slash}GCLR-Pad1)") (class "Default")
      (node (ref "U1") (pin "1") (pinfunction "I/GCLR_1") (pintype "bidirectional"))
    )
    (net (code "157") (name "unconnected-(U1-I{slash}OE1-Pad84)") (class "Default")
      (node (ref "U1") (pin "84") (pinfunction "I/OE1_84") (pintype "bidirectional"))
    )
    (net (code "158") (name "unconnected-(U1-I{slash}OE2{slash}GCLK2-Pad2)") (class "Default")
      (node (ref "U1") (pin "2") (pinfunction "I/OE2/GCLK2_2") (pintype "bidirectional"))
    )
    (net (code "159") (name "unconnected-(U1-MC13-Pad8)") (class "Default")
      (node (ref "U1") (pin "8") (pinfunction "MC13_8") (pintype "bidirectional"))
    )
    (net (code "160") (name "unconnected-(U1-MC14-Pad6)") (class "Default")
      (node (ref "U1") (pin "6") (pinfunction "MC14_6") (pintype "bidirectional"))
    )
    (net (code "161") (name "unconnected-(U1-MC15-Pad5)") (class "Default")
      (node (ref "U1") (pin "5") (pinfunction "MC15_5") (pintype "bidirectional"))
    )
    (net (code "162") (name "unconnected-(U1-MC16-Pad4)") (class "Default")
      (node (ref "U1") (pin "4") (pinfunction "MC16_4") (pintype "bidirectional"))
    )
    (net (code "163") (name "unconnected-(U1-MC33-Pad44)") (class "Default")
      (node (ref "U1") (pin "44") (pinfunction "MC33_44") (pintype "bidirectional"))
    )
    (net (code "164") (name "unconnected-(U1-MC50-Pad64)") (class "Default")
      (node (ref "U1") (pin "64") (pinfunction "MC50_64") (pintype "bidirectional"))
    )
    (net (code "165") (name "unconnected-(U1-MC58-Pad74)") (class "Default")
      (node (ref "U1") (pin "74") (pinfunction "MC58_74") (pintype "bidirectional"))
    )
    (net (code "166") (name "unconnected-(U1-MC63-Pad80)") (class "Default")
      (node (ref "U1") (pin "80") (pinfunction "MC63_80") (pintype "bidirectional"))
    )
    (net (code "167") (name "unconnected-(USB-Pad1)") (class "Default")
      (node (ref "USB") (pin "1") (pinfunction "1_1") (pintype "passive"))
    )
    (net (code "168") (name "unconnected-(USB-Pad4)") (class "Default")
      (node (ref "USB") (pin "4") (pinfunction "4_4") (pintype "passive"))
    )
    (net (code "169") (name "unconnected-(USB-Pad6)") (class "Default")
      (node (ref "USB") (pin "6") (pinfunction "6_6") (pintype "passive"))
    )
    (net (code "170") (name "unconnected-(USB-Pad7)") (class "Default")
      (node (ref "USB") (pin "7") (pinfunction "7_7") (pintype "passive"))
    )
    (net (code "171") (name "unconnected-(USB-Pad8)") (class "Default")
      (node (ref "USB") (pin "8") (pinfunction "8_8") (pintype "passive"))
    )
    (net (code "172") (name "unconnected-(USB-Pad9)") (class "Default")
      (node (ref "USB") (pin "9") (pinfunction "9_9") (pintype "passive"))
    )
    (net (code "173") (name "unconnected-(XO1-OE-Pad1)") (class "Default")
      (node (ref "XO1") (pin "1") (pinfunction "OE_1") (pintype "input"))
    )
  )
)
